# power_supply.net
KiCad netlist of a schematic drawn in Altium Designer
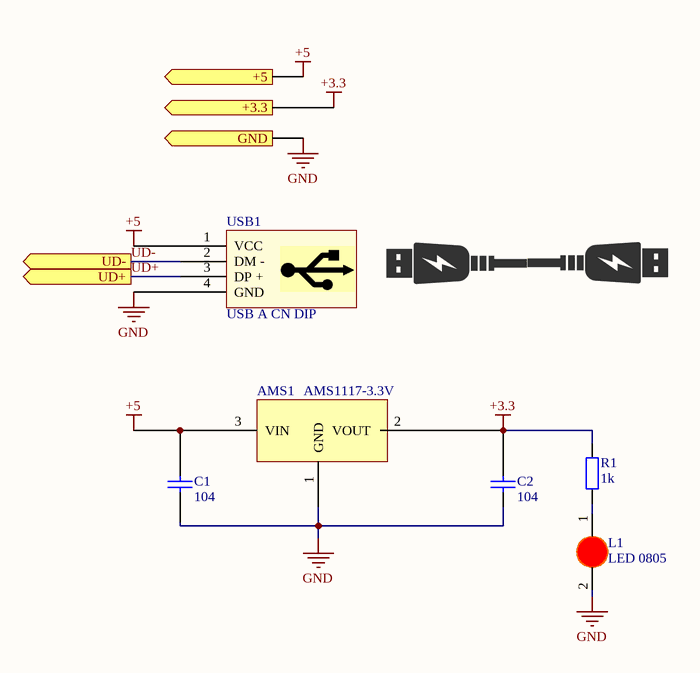
[diagram p0: power_supply.SchDoc]

(export (version "E")
  (design (tool "Eeschema 10.0.6"))
  (components
    (comp (ref "AMS1")
      (value "AMS1117-3.3V")
      (footprint "SOT223")
      (description "Dán")
      (libsource (lib "TrungVan_Lib") (part "AMS1117 SMD"))
    )
    (comp (ref "C1")
      (value "104")
      (footprint "tu 0603")
      (description "Dán")
      (libsource (lib "TrungVan_Lib") (part "Tu 0603 104 50V 10%"))
    )
    (comp (ref "C2")
      (value "104")
      (footprint "tu 0603")
      (description "Dán")
      (libsource (lib "TrungVan_Lib") (part "Tu 0603 104 50V 10%"))
    )
    (comp (ref "L1")
      (value "LED 0805")
      (footprint "LED-0805-Red")
      (description "Dán")
      (libsource (lib "TrungVan_Lib") (part "LED 0805 Do"))
    )
    (comp (ref "R1")
      (value "1k")
      (footprint "tro smd 0805")
      (description "Dán")
      (libsource (lib "TrungVan_Lib") (part "Tro 0805 1% 1k"))
    )
    (comp (ref "USB1")
      (value "USB A CN DIP")
      (footprint "USB A CN DIP")
      (description "USB Type A")
      (libsource (lib "TrungVan_Lib") (part "USB A CN DIP"))
    )
  )
  (nets
    (net (code "1") (name "+3.3") (class "Default")
      (node (ref "AMS1") (pin "2") (pinfunction "VOUT_2") (pintype "passive"))
      (node (ref "C2") (pin "1") (pinfunction "1_1") (pintype "passive"))
      (node (ref "R1") (pin "2") (pinfunction "2_2") (pintype "passive"))
    )
    (net (code "2") (name "+5") (class "Default")
      (node (ref "AMS1") (pin "3") (pinfunction "VIN_3") (pintype "passive"))
      (node (ref "C1") (pin "1") (pinfunction "1_1") (pintype "passive"))
      (node (ref "USB1") (pin "1") (pinfunction "VCC_1") (pintype "passive"))
    )
    (net (code "3") (name "/UD+") (class "Default")
      (node (ref "USB1") (pin "3") (pinfunction "DP_+_3") (pintype "passive"))
    )
    (net (code "4") (name "/UD-") (class "Default")
      (node (ref "USB1") (pin "2") (pinfunction "DM_-_2") (pintype "passive"))
    )
    (net (code "5") (name "GND") (class "Default")
      (node (ref "AMS1") (pin "1") (pinfunction "GND_1") (pintype "passive"))
      (node (ref "C1") (pin "2") (pinfunction "2_2") (pintype "passive"))
      (node (ref "C2") (pin "2") (pinfunction "2_2") (pintype "passive"))
      (node (ref "L1") (pin "2") (pinfunction "K_2") (pintype "passive"))
      (node (ref "USB1") (pin "4") (pinfunction "GND_4") (pintype "passive"))
    )
    (net (code "6") (name "Net-(L1-A)") (class "Default")
      (node (ref "L1") (pin "1") (pinfunction "A_1") (pintype "passive"))
      (node (ref "R1") (pin "1") (pinfunction "1_1") (pintype "passive"))
    )
  )
)
